# photo_coupling.net
KiCad netlist of a schematic drawn in Altium Designer
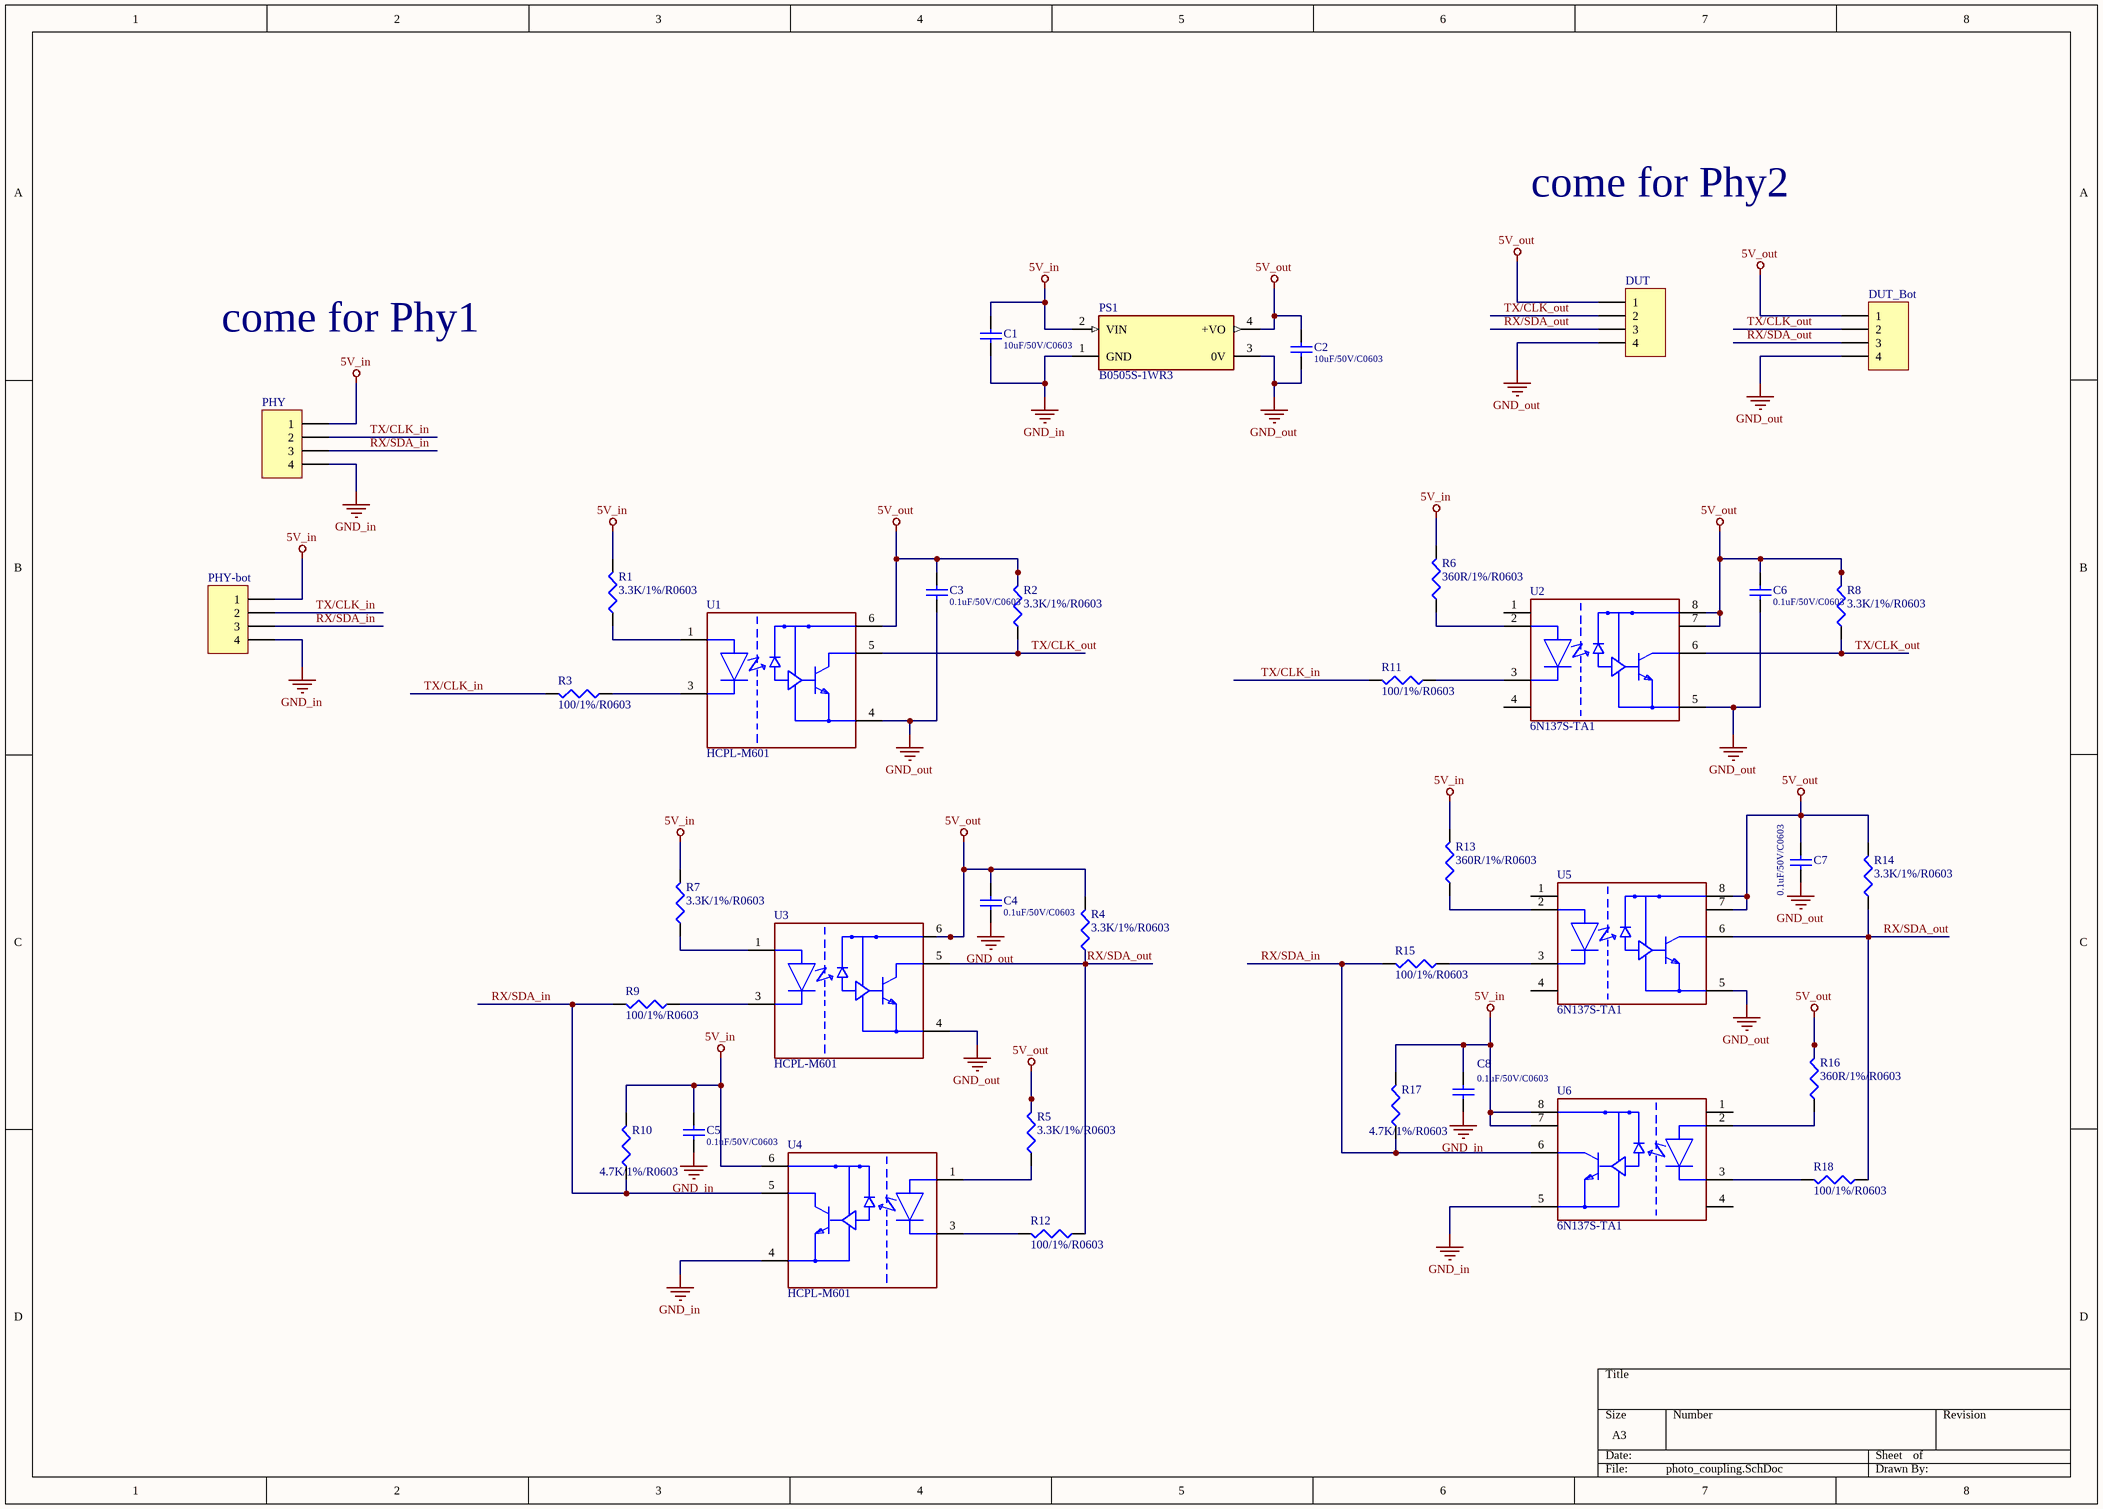
[diagram p0: photo_coupling.SchDoc]

(export (version "E")
  (design (tool "Eeschema 10.0.6"))
  (components
    (comp (ref "C1")
      (value "10uF/50V/C0603")
      (footprint "C0603")
      (description "MLCC 0603 0.1uF 50V 10% X7R")
      (fields (field (name "Comment") "0.1uF/50V/C0603"))
      (libsource (lib "Etica_LIB") (part "C0603 0.1uF 100V"))
    )
    (comp (ref "C2")
      (value "10uF/50V/C0603")
      (footprint "C0603")
      (description "MLCC 0603 0.1uF 50V 10% X7R")
      (fields (field (name "Comment") "0.1uF/50V/C0603"))
      (libsource (lib "Etica_LIB") (part "C0603 0.1uF 100V"))
    )
    (comp (ref "C3")
      (value "0.1uF/50V/C0603")
      (footprint "C0603")
      (description "MLCC 0603 0.1uF 50V 10% X7R")
      (libsource (lib "Etica_LIB") (part "C0603 0.1uF 100V"))
    )
    (comp (ref "C4")
      (value "0.1uF/50V/C0603")
      (footprint "C0603")
      (description "MLCC 0603 0.1uF 50V 10% X7R")
      (libsource (lib "Etica_LIB") (part "C0603 0.1uF 100V"))
    )
    (comp (ref "C5")
      (value "0.1uF/50V/C0603")
      (footprint "C0603")
      (description "MLCC 0603 0.1uF 50V 10% X7R")
      (libsource (lib "Etica_LIB") (part "C0603 0.1uF 100V"))
    )
    (comp (ref "C6")
      (value "0.1uF/50V/C0603")
      (footprint "C0603")
      (description "MLCC 0603 0.1uF 50V 10% X7R")
      (libsource (lib "Etica_LIB") (part "C0603 0.1uF 100V"))
    )
    (comp (ref "C7")
      (value "0.1uF/50V/C0603")
      (footprint "C0603")
      (description "MLCC 0603 0.1uF 50V 10% X7R")
      (libsource (lib "Etica_LIB") (part "C0603 0.1uF 100V"))
    )
    (comp (ref "C8")
      (value "0.1uF/50V/C0603")
      (footprint "C0603")
      (description "MLCC 0603 0.1uF 50V 10% X7R")
      (libsource (lib "Etica_LIB") (part "C0603 0.1uF 100V"))
    )
    (comp (ref "DUT")
      (value "CCX-W125-04-SMT")
      (footprint "CON1.25MM_4PIN(180)")
      (libsource (lib "") (part "Pitch 1.25 mm/ 180° / 4 pin_1"))
    )
    (comp (ref "DUT_Bot")
      (value "CCX-W125-04-SMT")
      (footprint "CON1.25MM_4PIN(180)")
      (libsource (lib "") (part "Pitch 1.25 mm/ 180° / 4 pin_1"))
    )
    (comp (ref "PHY")
      (value "CCX-W125-04-SMT")
      (footprint "CON1.25MM_4PIN(180)")
      (libsource (lib "Etica_LIB") (part "Pitch 1.25 mm/ 180° / 4 pin"))
    )
    (comp (ref "PHY-bot")
      (value "CCX-W125-04-SMT")
      (footprint "CON1.25MM_4PIN(180)")
      (libsource (lib "Etica_LIB") (part "Pitch 1.25 mm/ 180° / 4 pin"))
    )
    (comp (ref "PS1")
      (value "B0505S-1WR3")
      (footprint "CONV_B0505S-1WR3")
      (description "Isolated Module DC DC Converter 1 Output 5V - - - 200mA 4.5V - 5.5V Input")
      (fields (field (name "MF") "Mornsun America, LLC"))
      (libsource (lib "Etica_LIB") (part "B0505S-1WR3"))
    )
    (comp (ref "R1")
      (value "3.3K/1%/R0603")
      (footprint "R0603")
      (description "Res 0603 3.3K 1% 1/10w")
      (libsource (lib "Etica_LIB") (part "R0603 3.3k 1% 1/10w"))
    )
    (comp (ref "R2")
      (value "3.3K/1%/R0603")
      (footprint "R0603")
      (description "Res 0603 3.3K 1% 1/10w")
      (libsource (lib "Etica_LIB") (part "R0603 3.3k 1% 1/10w"))
    )
    (comp (ref "R3")
      (value "100/1%/R0603")
      (footprint "R0603")
      (description "Res 0603 3.3K 1% 1/10w")
      (fields (field (name "Comment") "3.3K/1%/R0603"))
      (libsource (lib "Etica_LIB") (part "R0603 3.3k 1% 1/10w"))
    )
    (comp (ref "R4")
      (value "3.3K/1%/R0603")
      (footprint "R0603")
      (description "Res 0603 3.3K 1% 1/10w")
      (libsource (lib "Etica_LIB") (part "R0603 3.3k 1% 1/10w"))
    )
    (comp (ref "R5")
      (value "3.3K/1%/R0603")
      (footprint "R0603")
      (description "Res 0603 3.3K 1% 1/10w")
      (libsource (lib "Etica_LIB") (part "R0603 3.3k 1% 1/10w"))
    )
    (comp (ref "R6")
      (value "360R/1%/R0603")
      (footprint "R0603")
      (description "Res 0603 3.3K 1% 1/10w")
      (fields (field (name "Comment") "3.3K/1%/R0603"))
      (libsource (lib "Etica_LIB") (part "R0603 3.3k 1% 1/10w"))
    )
    (comp (ref "R7")
      (value "3.3K/1%/R0603")
      (footprint "R0603")
      (description "Res 0603 3.3K 1% 1/10w")
      (libsource (lib "Etica_LIB") (part "R0603 3.3k 1% 1/10w"))
    )
    (comp (ref "R8")
      (value "3.3K/1%/R0603")
      (footprint "R0603")
      (description "Res 0603 3.3K 1% 1/10w")
      (libsource (lib "Etica_LIB") (part "R0603 3.3k 1% 1/10w"))
    )
    (comp (ref "R9")
      (value "100/1%/R0603")
      (footprint "R0603")
      (description "Res 0603 3.3K 1% 1/10w")
      (fields (field (name "Comment") "3.3K/1%/R0603"))
      (libsource (lib "Etica_LIB") (part "R0603 3.3k 1% 1/10w"))
    )
    (comp (ref "R10")
      (value "4.7K/1%/R0603")
      (footprint "R0603")
      (description "Res 0603 3.3K 1% 1/10w")
      (fields (field (name "Comment") "3.3K/1%/R0603"))
      (libsource (lib "Etica_LIB") (part "R0603 3.3k 1% 1/10w"))
    )
    (comp (ref "R11")
      (value "100/1%/R0603")
      (footprint "R0603")
      (description "Res 0603 3.3K 1% 1/10w")
      (fields (field (name "Comment") "3.3K/1%/R0603"))
      (libsource (lib "Etica_LIB") (part "R0603 3.3k 1% 1/10w"))
    )
    (comp (ref "R12")
      (value "100/1%/R0603")
      (footprint "R0603")
      (description "Res 0603 3.3K 1% 1/10w")
      (fields (field (name "Comment") "3.3K/1%/R0603"))
      (libsource (lib "Etica_LIB") (part "R0603 3.3k 1% 1/10w"))
    )
    (comp (ref "R13")
      (value "360R/1%/R0603")
      (footprint "R0603")
      (description "Res 0603 3.3K 1% 1/10w")
      (fields (field (name "Comment") "3.3K/1%/R0603"))
      (libsource (lib "Etica_LIB") (part "R0603 3.3k 1% 1/10w"))
    )
    (comp (ref "R14")
      (value "3.3K/1%/R0603")
      (footprint "R0603")
      (description "Res 0603 3.3K 1% 1/10w")
      (libsource (lib "Etica_LIB") (part "R0603 3.3k 1% 1/10w"))
    )
    (comp (ref "R15")
      (value "100/1%/R0603")
      (footprint "R0603")
      (description "Res 0603 3.3K 1% 1/10w")
      (fields (field (name "Comment") "3.3K/1%/R0603"))
      (libsource (lib "Etica_LIB") (part "R0603 3.3k 1% 1/10w"))
    )
    (comp (ref "R16")
      (value "360R/1%/R0603")
      (footprint "R0603")
      (description "Res 0603 3.3K 1% 1/10w")
      (fields (field (name "Comment") "3.3K/1%/R0603"))
      (libsource (lib "Etica_LIB") (part "R0603 3.3k 1% 1/10w"))
    )
    (comp (ref "R17")
      (value "4.7K/1%/R0603")
      (footprint "R0603")
      (description "Res 0603 3.3K 1% 1/10w")
      (fields (field (name "Comment") "3.3K/1%/R0603"))
      (libsource (lib "Etica_LIB") (part "R0603 3.3k 1% 1/10w"))
    )
    (comp (ref "R18")
      (value "100/1%/R0603")
      (footprint "R0603")
      (description "Res 0603 3.3K 1% 1/10w")
      (fields (field (name "Comment") "3.3K/1%/R0603"))
      (libsource (lib "Etica_LIB") (part "R0603 3.3k 1% 1/10w"))
    )
    (comp (ref "U1")
      (value "HCPL-M601")
      (footprint "Etica_PCB_Lib:JEDEC_MO-155")
      (description "Small Outline, 5 Lead, High CMR,\r\nHigh Speed, Logic Gate Optocouplers")
      (libsource (lib "Etica_LIB") (part "HCPL-M601"))
    )
    (comp (ref "U2")
      (value "6N137S-TA1")
      (footprint "SOP254P1016X460-8N")
      (description "Small Outline, 8 Lead, High CMR,\r\nHigh Speed, Logic Gate Optocouplers")
      (libsource (lib "Etica_LIB") (part "6N137S-TA1"))
    )
    (comp (ref "U3")
      (value "HCPL-M601")
      (footprint "Etica_PCB_Lib:JEDEC_MO-155")
      (description "Small Outline, 5 Lead, High CMR,\r\nHigh Speed, Logic Gate Optocouplers")
      (libsource (lib "Etica_LIB") (part "HCPL-M601"))
    )
    (comp (ref "U4")
      (value "HCPL-M601")
      (footprint "Etica_PCB_Lib:JEDEC_MO-155")
      (description "Small Outline, 5 Lead, High CMR,\r\nHigh Speed, Logic Gate Optocouplers")
      (libsource (lib "Etica_LIB") (part "HCPL-M601"))
    )
    (comp (ref "U5")
      (value "6N137S-TA1")
      (footprint "SOP254P1016X460-8N")
      (description "Small Outline, 8 Lead, High CMR,\r\nHigh Speed, Logic Gate Optocouplers")
      (libsource (lib "Etica_LIB") (part "6N137S-TA1"))
    )
    (comp (ref "U6")
      (value "6N137S-TA1")
      (footprint "SOP254P1016X460-8N")
      (description "Small Outline, 8 Lead, High CMR,\r\nHigh Speed, Logic Gate Optocouplers")
      (libsource (lib "Etica_LIB") (part "6N137S-TA1"))
    )
  )
  (nets
    (net (code "1") (name "/RX{slash}SDA_in") (class "Default")
      (node (ref "PHY") (pin "3") (pinfunction "3_3") (pintype "passive"))
      (node (ref "PHY-bot") (pin "3") (pinfunction "3_3") (pintype "passive"))
      (node (ref "R10") (pin "1") (pinfunction "1_1") (pintype "passive"))
      (node (ref "R15") (pin "2") (pinfunction "2_2") (pintype "passive"))
      (node (ref "R17") (pin "1") (pinfunction "1_1") (pintype "passive"))
      (node (ref "R9") (pin "2") (pinfunction "2_2") (pintype "passive"))
      (node (ref "U4") (pin "5") (pinfunction "V01_5") (pintype "passive"))
      (node (ref "U6") (pin "6") (pinfunction "V01_6") (pintype "passive"))
    )
    (net (code "2") (name "/RX{slash}SDA_out") (class "Default")
      (node (ref "DUT") (pin "3") (pinfunction "3_3") (pintype "passive"))
      (node (ref "DUT_Bot") (pin "3") (pinfunction "3_3") (pintype "passive"))
      (node (ref "R12") (pin "1") (pinfunction "1_1") (pintype "passive"))
      (node (ref "R14") (pin "1") (pinfunction "1_1") (pintype "passive"))
      (node (ref "R18") (pin "1") (pinfunction "1_1") (pintype "passive"))
      (node (ref "R4") (pin "1") (pinfunction "1_1") (pintype "passive"))
      (node (ref "U3") (pin "5") (pinfunction "V01_5") (pintype "passive"))
      (node (ref "U5") (pin "6") (pinfunction "V01_6") (pintype "passive"))
    )
    (net (code "3") (name "/TX{slash}CLK_in") (class "Default")
      (node (ref "PHY") (pin "2") (pinfunction "2_2") (pintype "passive"))
      (node (ref "PHY-bot") (pin "2") (pinfunction "2_2") (pintype "passive"))
      (node (ref "R11") (pin "2") (pinfunction "2_2") (pintype "passive"))
      (node (ref "R3") (pin "2") (pinfunction "2_2") (pintype "passive"))
    )
    (net (code "4") (name "/TX{slash}CLK_out") (class "Default")
      (node (ref "DUT") (pin "2") (pinfunction "2_2") (pintype "passive"))
      (node (ref "DUT_Bot") (pin "2") (pinfunction "2_2") (pintype "passive"))
      (node (ref "R2") (pin "1") (pinfunction "1_1") (pintype "passive"))
      (node (ref "R8") (pin "1") (pinfunction "1_1") (pintype "passive"))
      (node (ref "U1") (pin "5") (pinfunction "V01_5") (pintype "passive"))
      (node (ref "U2") (pin "6") (pinfunction "V01_6") (pintype "passive"))
    )
    (net (code "5") (name "5V_in") (class "Default")
      (node (ref "C1") (pin "2") (pinfunction "2_2") (pintype "passive"))
      (node (ref "C5") (pin "2") (pinfunction "2_2") (pintype "passive"))
      (node (ref "C8") (pin "2") (pinfunction "2_2") (pintype "passive"))
      (node (ref "PHY") (pin "1") (pinfunction "1_1") (pintype "passive"))
      (node (ref "PHY-bot") (pin "1") (pinfunction "1_1") (pintype "passive"))
      (node (ref "PS1") (pin "2") (pinfunction "VIN_2") (pintype "input"))
      (node (ref "R1") (pin "2") (pinfunction "2_2") (pintype "passive"))
      (node (ref "R10") (pin "2") (pinfunction "2_2") (pintype "passive"))
      (node (ref "R13") (pin "2") (pinfunction "2_2") (pintype "passive"))
      (node (ref "R17") (pin "2") (pinfunction "2_2") (pintype "passive"))
      (node (ref "R6") (pin "2") (pinfunction "2_2") (pintype "passive"))
      (node (ref "R7") (pin "2") (pinfunction "2_2") (pintype "passive"))
      (node (ref "U4") (pin "6") (pinfunction "VCC_6") (pintype "power_in"))
      (node (ref "U6") (pin "7") (pinfunction "VE_7") (pintype "power_in"))
      (node (ref "U6") (pin "8") (pinfunction "VCC_8") (pintype "power_in"))
    )
    (net (code "6") (name "5V_out") (class "Default")
      (node (ref "C2") (pin "2") (pinfunction "2_2") (pintype "passive"))
      (node (ref "C3") (pin "2") (pinfunction "2_2") (pintype "passive"))
      (node (ref "C4") (pin "2") (pinfunction "2_2") (pintype "passive"))
      (node (ref "C6") (pin "2") (pinfunction "2_2") (pintype "passive"))
      (node (ref "C7") (pin "2") (pinfunction "2_2") (pintype "passive"))
      (node (ref "DUT") (pin "1") (pinfunction "1_1") (pintype "passive"))
      (node (ref "DUT_Bot") (pin "1") (pinfunction "1_1") (pintype "passive"))
      (node (ref "PS1") (pin "4") (pinfunction "+VO_4") (pintype "output"))
      (node (ref "R14") (pin "2") (pinfunction "2_2") (pintype "passive"))
      (node (ref "R16") (pin "2") (pinfunction "2_2") (pintype "passive"))
      (node (ref "R2") (pin "2") (pinfunction "2_2") (pintype "passive"))
      (node (ref "R4") (pin "2") (pinfunction "2_2") (pintype "passive"))
      (node (ref "R5") (pin "2") (pinfunction "2_2") (pintype "passive"))
      (node (ref "R8") (pin "2") (pinfunction "2_2") (pintype "passive"))
      (node (ref "U1") (pin "6") (pinfunction "VCC_6") (pintype "power_in"))
      (node (ref "U2") (pin "7") (pinfunction "VE_7") (pintype "power_in"))
      (node (ref "U2") (pin "8") (pinfunction "VCC_8") (pintype "power_in"))
      (node (ref "U3") (pin "6") (pinfunction "VCC_6") (pintype "power_in"))
      (node (ref "U5") (pin "7") (pinfunction "VE_7") (pintype "power_in"))
      (node (ref "U5") (pin "8") (pinfunction "VCC_8") (pintype "power_in"))
    )
    (net (code "7") (name "GND_in") (class "Default")
      (node (ref "C1") (pin "1") (pinfunction "1_1") (pintype "passive"))
      (node (ref "C5") (pin "1") (pinfunction "1_1") (pintype "passive"))
      (node (ref "C8") (pin "1") (pinfunction "1_1") (pintype "passive"))
      (node (ref "PHY") (pin "4") (pinfunction "4_4") (pintype "passive"))
      (node (ref "PHY-bot") (pin "4") (pinfunction "4_4") (pintype "passive"))
      (node (ref "PS1") (pin "1") (pinfunction "GND_1") (pintype "power_in"))
      (node (ref "U4") (pin "4") (pinfunction "GND_4") (pintype "power_in"))
      (node (ref "U6") (pin "5") (pinfunction "GND_5") (pintype "power_in"))
    )
    (net (code "8") (name "GND_out") (class "Default")
      (node (ref "C2") (pin "1") (pinfunction "1_1") (pintype "passive"))
      (node (ref "C3") (pin "1") (pinfunction "1_1") (pintype "passive"))
      (node (ref "C4") (pin "1") (pinfunction "1_1") (pintype "passive"))
      (node (ref "C6") (pin "1") (pinfunction "1_1") (pintype "passive"))
      (node (ref "C7") (pin "1") (pinfunction "1_1") (pintype "passive"))
      (node (ref "DUT") (pin "4") (pinfunction "4_4") (pintype "passive"))
      (node (ref "DUT_Bot") (pin "4") (pinfunction "4_4") (pintype "passive"))
      (node (ref "PS1") (pin "3") (pinfunction "0V_3") (pintype "passive"))
      (node (ref "U1") (pin "4") (pinfunction "GND_4") (pintype "power_in"))
      (node (ref "U2") (pin "5") (pinfunction "GND_5") (pintype "power_in"))
      (node (ref "U3") (pin "4") (pinfunction "GND_4") (pintype "power_in"))
      (node (ref "U5") (pin "5") (pinfunction "GND_5") (pintype "power_in"))
    )
    (net (code "9") (name "Net-(U1-VF1+)") (class "Default")
      (node (ref "R1") (pin "1") (pinfunction "1_1") (pintype "passive"))
      (node (ref "U1") (pin "1") (pinfunction "VF1+_1") (pintype "passive"))
    )
    (net (code "10") (name "Net-(U1-VF1-)") (class "Default")
      (node (ref "R3") (pin "1") (pinfunction "1_1") (pintype "passive"))
      (node (ref "U1") (pin "3") (pinfunction "VF1-_3") (pintype "passive"))
    )
    (net (code "11") (name "Net-(U2-VF1+)") (class "Default")
      (node (ref "R6") (pin "1") (pinfunction "1_1") (pintype "passive"))
      (node (ref "U2") (pin "2") (pinfunction "VF1+_2") (pintype "passive"))
    )
    (net (code "12") (name "Net-(U2-VF1-)") (class "Default")
      (node (ref "R11") (pin "1") (pinfunction "1_1") (pintype "passive"))
      (node (ref "U2") (pin "3") (pinfunction "VF1-_3") (pintype "passive"))
    )
    (net (code "13") (name "Net-(U3-VF1+)") (class "Default")
      (node (ref "R7") (pin "1") (pinfunction "1_1") (pintype "passive"))
      (node (ref "U3") (pin "1") (pinfunction "VF1+_1") (pintype "passive"))
    )
    (net (code "14") (name "Net-(U3-VF1-)") (class "Default")
      (node (ref "R9") (pin "1") (pinfunction "1_1") (pintype "passive"))
      (node (ref "U3") (pin "3") (pinfunction "VF1-_3") (pintype "passive"))
    )
    (net (code "15") (name "Net-(U4-VF1+)") (class "Default")
      (node (ref "R5") (pin "1") (pinfunction "1_1") (pintype "passive"))
      (node (ref "U4") (pin "1") (pinfunction "VF1+_1") (pintype "passive"))
    )
    (net (code "16") (name "Net-(U4-VF1-)") (class "Default")
      (node (ref "R12") (pin "2") (pinfunction "2_2") (pintype "passive"))
      (node (ref "U4") (pin "3") (pinfunction "VF1-_3") (pintype "passive"))
    )
    (net (code "17") (name "Net-(U5-VF1+)") (class "Default")
      (node (ref "R13") (pin "1") (pinfunction "1_1") (pintype "passive"))
      (node (ref "U5") (pin "2") (pinfunction "VF1+_2") (pintype "passive"))
    )
    (net (code "18") (name "Net-(U5-VF1-)") (class "Default")
      (node (ref "R15") (pin "1") (pinfunction "1_1") (pintype "passive"))
      (node (ref "U5") (pin "3") (pinfunction "VF1-_3") (pintype "passive"))
    )
    (net (code "19") (name "Net-(U6-VF1+)") (class "Default")
      (node (ref "R16") (pin "1") (pinfunction "1_1") (pintype "passive"))
      (node (ref "U6") (pin "2") (pinfunction "VF1+_2") (pintype "passive"))
    )
    (net (code "20") (name "Net-(U6-VF1-)") (class "Default")
      (node (ref "R18") (pin "2") (pinfunction "2_2") (pintype "passive"))
      (node (ref "U6") (pin "3") (pinfunction "VF1-_3") (pintype "passive"))
    )
    (net (code "21") (name "unconnected-(U2-NC-Pad1)") (class "Default")
      (node (ref "U2") (pin "1") (pinfunction "NC_1") (pintype "passive"))
    )
    (net (code "22") (name "unconnected-(U2-NC-Pad4)") (class "Default")
      (node (ref "U2") (pin "4") (pinfunction "NC_4") (pintype "passive"))
    )
    (net (code "23") (name "unconnected-(U5-NC-Pad1)") (class "Default")
      (node (ref "U5") (pin "1") (pinfunction "NC_1") (pintype "passive"))
    )
    (net (code "24") (name "unconnected-(U5-NC-Pad4)") (class "Default")
      (node (ref "U5") (pin "4") (pinfunction "NC_4") (pintype "passive"))
    )
    (net (code "25") (name "unconnected-(U6-NC-Pad1)") (class "Default")
      (node (ref "U6") (pin "1") (pinfunction "NC_1") (pintype "passive"))
    )
    (net (code "26") (name "unconnected-(U6-NC-Pad4)") (class "Default")
      (node (ref "U6") (pin "4") (pinfunction "NC_4") (pintype "passive"))
    )
  )
)
